# MODBUS_TO_UART.net
KiCad netlist of a schematic drawn in Altium Designer
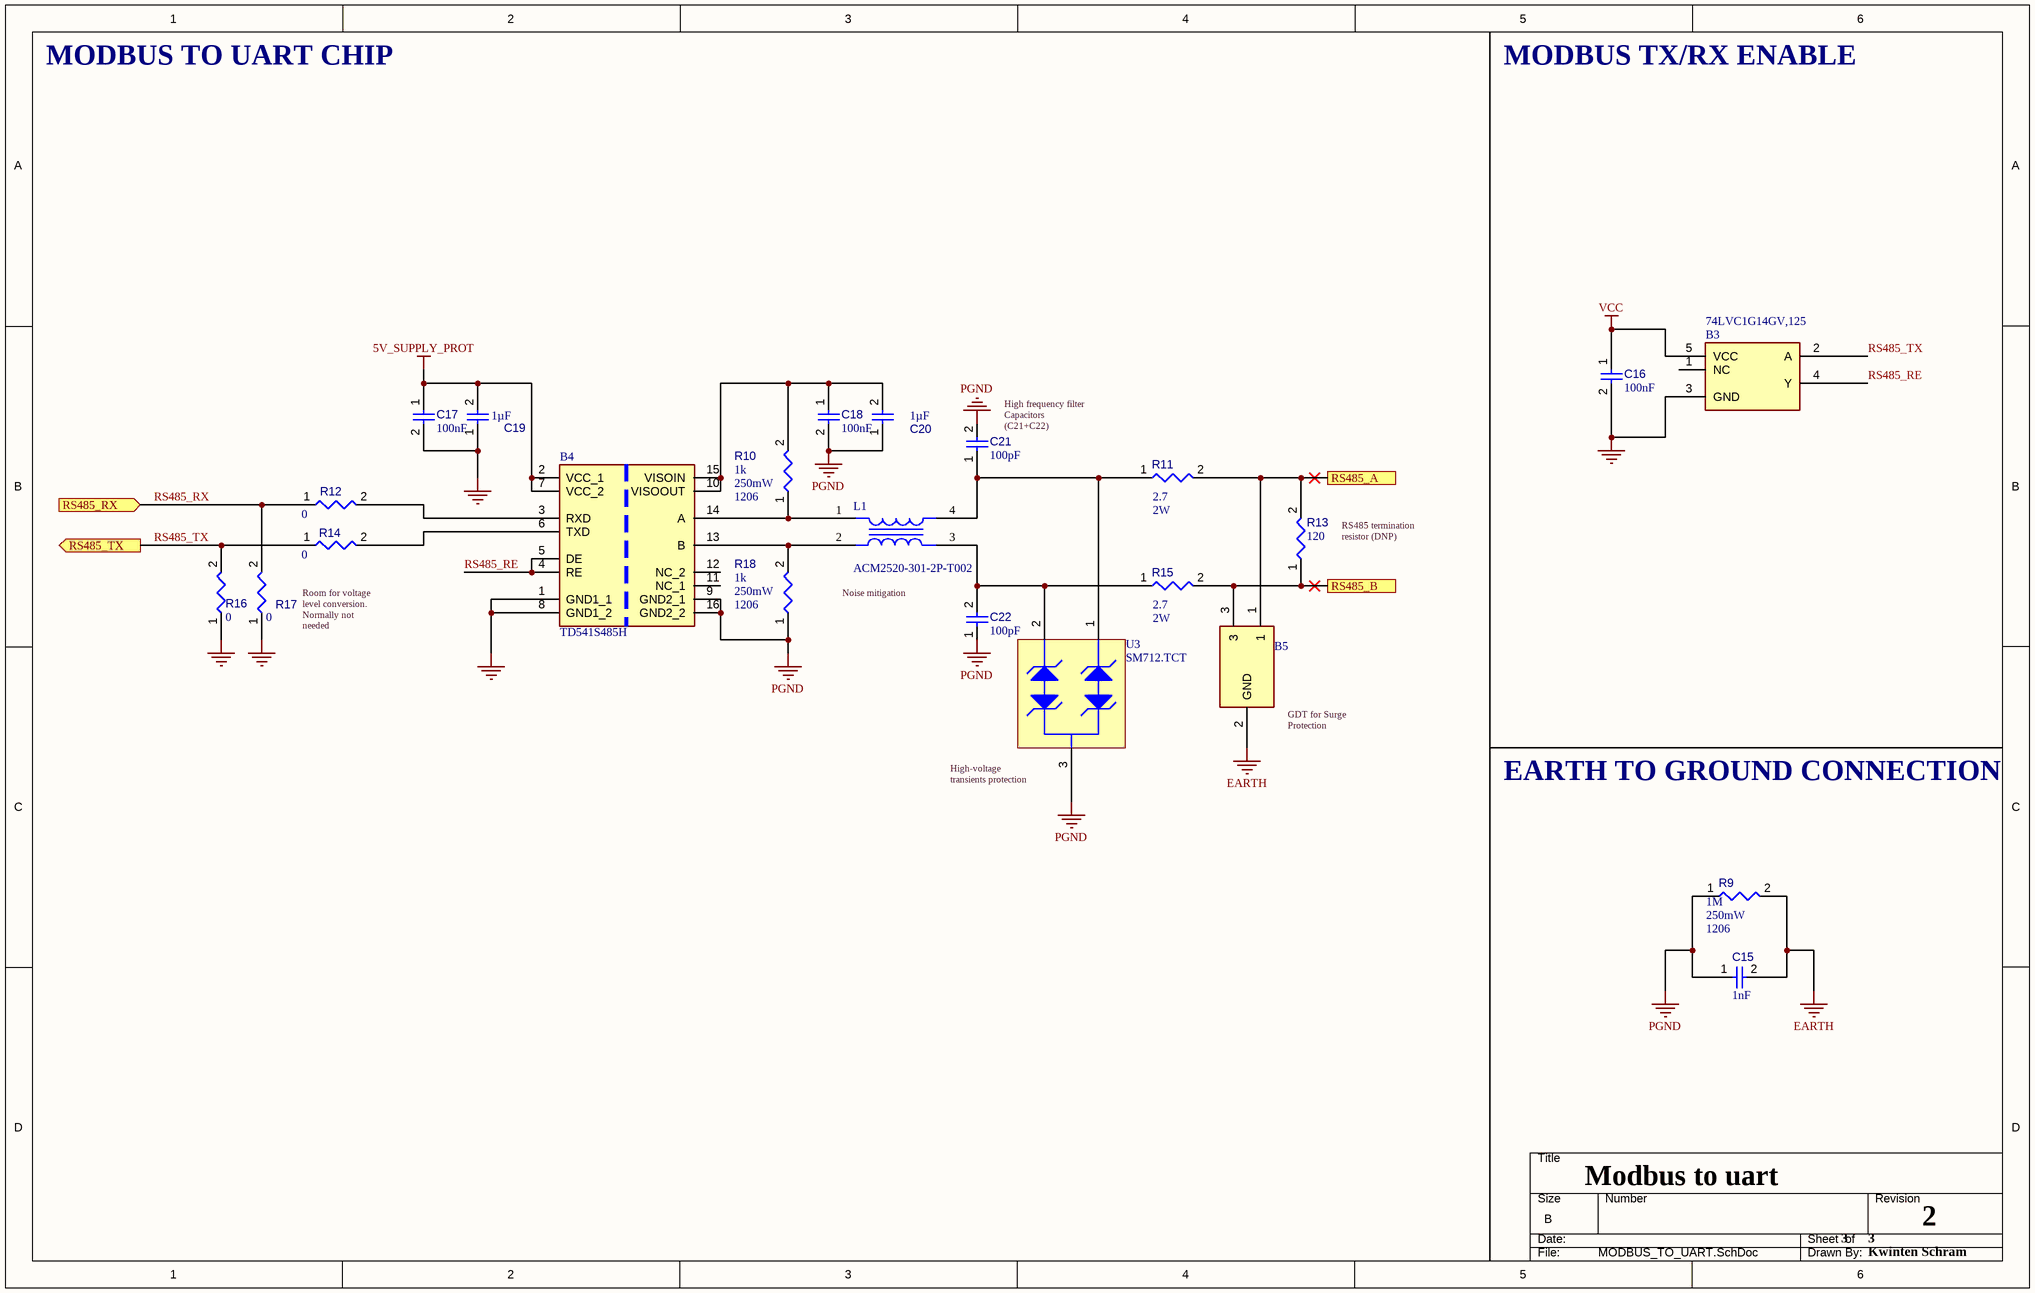
[diagram p0: MODBUS_TO_UART.SchDoc]

(export (version "E")
  (design (tool "Eeschema 10.0.6"))
  (components
    (comp (ref "B3")
      (value "74LVC1G14GV,125")
      (footprint "74LVC1G14GV,125-Footprint-1")
      (description "Inverter, LVC/LCX/Z Series, 1-Func, 1-Input, CMOS, PDSO5")
      (libsource (lib "Altium Concord Pro on A365") (part "74LVC1G14GV,125-Symbol-1"))
    )
    (comp (ref "B4")
      (value "TD541S485H")
      (footprint "TD541S485H-Footprint-1")
      (description "Support Circuit")
      (libsource (lib "Altium Concord Pro on A365") (part "TD541S485H-Symbol-1"))
    )
    (comp (ref "B5")
      (value "3RL090M-5-S")
      (footprint "2036-09-SM-RPLF-H-Footprint-1")
      (description "3R-5-S Series 5 mm 600 V 5 kA Surface Mount Gas Discharge Tube")
      (libsource (lib "Altium Concord Pro on A365") (part "2036-09-SM-RPLF-H-Symbol-1"))
    )
    (comp (ref "C15")
      (value "1nF")
      (footprint "FP-CC1206-0_3-1_45-IPC_A")
      (fields (field (name "TOLERANCE") "10%") (field (name "Comment") "CC1206KKX7RDBB102"))
      (libsource (lib "Altium Concord Pro on A365") (part "CAP-NP-2"))
    )
    (comp (ref "C16")
      (value "100nF")
      (footprint "FP-0603-L_1_6_0_15-W_0_81-MFG")
      (fields (field (name "TOLERANCE") "10%") (field (name "Comment") "06033C104KAT2A"))
      (libsource (lib "Altium Concord Pro on A365") (part "CAP-NP-2"))
    )
    (comp (ref "C17")
      (value "100nF")
      (footprint "FP-0603-L_1_6_0_15-W_0_81-MFG")
      (fields (field (name "TOLERANCE") "10%") (field (name "Comment") "06033C104KAT2A"))
      (libsource (lib "Altium Concord Pro on A365") (part "CAP-NP-2"))
    )
    (comp (ref "C18")
      (value "100nF")
      (footprint "FP-0603-L_1_6_0_15-W_0_81-MFG")
      (fields (field (name "TOLERANCE") "10%") (field (name "Comment") "06033C104KAT2A"))
      (libsource (lib "Altium Concord Pro on A365") (part "CAP-NP-2"))
    )
    (comp (ref "C19")
      (value "1µF")
      (footprint "FP-CC0603-DA-MFG")
      (fields (field (name "TOLERANCE") "10%") (field (name "Comment") "CC0603KPX7R8BB105"))
      (libsource (lib "Altium Concord Pro on A365") (part "CAP-NP-2"))
    )
    (comp (ref "C20")
      (value "1µF")
      (footprint "FP-CC0603-DA-MFG")
      (fields (field (name "TOLERANCE") "10%") (field (name "Comment") "CC0603KPX7R8BB105"))
      (libsource (lib "Altium Concord Pro on A365") (part "CAP-NP-2"))
    )
    (comp (ref "C21")
      (value "100pF")
      (footprint "FP-CC0603-DA-IPC_B")
      (fields (field (name "TOLERANCE") "10%") (field (name "Comment") "CC0603KRX7R9BB101"))
      (libsource (lib "Altium Concord Pro on A365") (part "CAP-NP-2"))
    )
    (comp (ref "C22")
      (value "100pF")
      (footprint "FP-CC0603-DA-IPC_B")
      (fields (field (name "TOLERANCE") "10%") (field (name "Comment") "CC0603KRX7R9BB101"))
      (libsource (lib "Altium Concord Pro on A365") (part "CAP-NP-2"))
    )
    (comp (ref "L1")
      (value "ACM2520-301-2P-T002")
      (footprint "FP-ACM2520-2P-MFG")
      (description "Ferrite Chip, 2 Function(s), 20V, 0.4A, 4 Pin(s)")
      (libsource (lib "Altium Concord Pro on A365") (part "d0b2d54a63b95a1e21836838efe74ed"))
    )
    (comp (ref "R9")
      (value "1M")
      (footprint "RESC3116X65X40ML10T20")
      (description "Fixed Resistor, Thin Film, 0.25W, 1000000ohm, 200V, 1% +/-Tol, 50ppm/Cel, Surface Mount, 1206")
      (fields
        (field (name "POWER") "250mW")
        (field (name "TOLERANCE") "1%")
        (field (name "CASE/PACKAGE") "1206")
        (field (name "Comment") "RT1206FRE071ML")
      )
      (libsource (lib "Altium Concord Pro on A365") (part "RES-2"))
    )
    (comp (ref "R10")
      (value "1k")
      (footprint "FP-CRCW1206-e3-IPC_A")
      (fields
        (field (name "CASE/PACKAGE") "1206")
        (field (name "TOLERANCE") "5%")
        (field (name "POWER") "250mW")
        (field (name "Comment") "CRCW12061K00JNEC")
      )
      (libsource (lib "Altium Concord Pro on A365") (part "RES-2"))
    )
    (comp (ref "R11")
      (value "2.7")
      (footprint "SMW22R7JT-Footprint-1")
      (description "Fixed Resistor, Wire Wound, 2W, 2.7ohm, 300V, 5% +/-Tol, 200ppm/Cel, Surface Mount, 2616")
      (fields
        (field (name "POWER") "2W")
        (field (name "TOLERANCE") "5%")
        (field (name "Comment") "SMW22R7JT")
      )
      (libsource (lib "Altium Concord Pro on A365") (part "RES-2"))
    )
    (comp (ref "R12")
      (value "0")
      (footprint "FP-CRCW0402-e3-IPC_A")
      (description "Metal Glaze/thick Film, 0.063W, 0ohm, Surface Mount, 0402")
      (fields (field (name "POWER") "63mW") (field (name "Comment") "CRCW04020000Z0ED"))
      (libsource (lib "Altium Concord Pro on A365") (part "RES-2"))
    )
    (comp (ref "R13")
      (value "120")
      (footprint "FP-RT0603-IPC_C")
      (description "Fixed Resistor, Thin Film, 0.1W, 120ohm, 75V, 0.5% +/-Tol, 50ppm/Cel, Surface Mount, 0603")
      (fields (field (name "TOLERANCE") "0.5%") (field (name "POWER") "100mW"))
      (libsource (lib "Altium Concord Pro on A365") (part "RES-2"))
    )
    (comp (ref "R14")
      (value "0")
      (footprint "FP-CRCW0402-e3-IPC_A")
      (description "Metal Glaze/thick Film, 0.063W, 0ohm, Surface Mount, 0402")
      (fields (field (name "POWER") "63mW") (field (name "Comment") "CRCW04020000Z0ED"))
      (libsource (lib "Altium Concord Pro on A365") (part "RES-2"))
    )
    (comp (ref "R15")
      (value "2.7")
      (footprint "SMW22R7JT-Footprint-1")
      (description "Fixed Resistor, Wire Wound, 2W, 2.7ohm, 300V, 5% +/-Tol, 200ppm/Cel, Surface Mount, 2616")
      (fields
        (field (name "POWER") "2W")
        (field (name "TOLERANCE") "5%")
        (field (name "Comment") "SMW22R7JT")
      )
      (libsource (lib "Altium Concord Pro on A365") (part "RES-2"))
    )
    (comp (ref "R16")
      (value "0")
      (footprint "FP-CRCW0402-e3-IPC_A")
      (description "Metal Glaze/thick Film, 0.063W, 0ohm, Surface Mount, 0402")
      (fields (field (name "POWER") "63mW") (field (name "Comment") "CRCW04020000Z0ED"))
      (libsource (lib "Altium Concord Pro on A365") (part "RES-2"))
    )
    (comp (ref "R17")
      (value "0")
      (footprint "FP-CRCW0402-e3-IPC_A")
      (description "Metal Glaze/thick Film, 0.063W, 0ohm, Surface Mount, 0402")
      (fields (field (name "POWER") "63mW") (field (name "Comment") "CRCW04020000Z0ED"))
      (libsource (lib "Altium Concord Pro on A365") (part "RES-2"))
    )
    (comp (ref "R18")
      (value "1k")
      (footprint "FP-CRCW1206-e3-IPC_A")
      (fields
        (field (name "CASE/PACKAGE") "1206")
        (field (name "TOLERANCE") "5%")
        (field (name "POWER") "250mW")
        (field (name "Comment") "CRCW12061K00JNEC")
      )
      (libsource (lib "Altium Concord Pro on A365") (part "RES-2"))
    )
    (comp (ref "U3")
      (value "SM712.TCT")
      (footprint "SMTC-SOT23-3_V")
      (description "Trans Voltage Suppressor Diode, 400W, 12V V(RWM), Unidirectional, 4 Element, Silicon")
      (libsource (lib "Altium Concord Pro on A365") (part "SMTC-SM712.TCT-SOT23-3"))
    )
  )
  (nets
    (net (code "1") (name "/RS485_A") (class "Default")
      (node (ref "B5") (pin "1") (pinfunction "1_1") (pintype "passive"))
      (node (ref "R11") (pin "2") (pinfunction "2_2") (pintype "passive"))
      (node (ref "R13") (pin "2") (pinfunction "2_2") (pintype "passive"))
    )
    (net (code "2") (name "/RS485_B") (class "Default")
      (node (ref "B5") (pin "3") (pinfunction "3_3") (pintype "passive"))
      (node (ref "R13") (pin "1") (pinfunction "1_1") (pintype "passive"))
      (node (ref "R15") (pin "2") (pinfunction "2_2") (pintype "passive"))
    )
    (net (code "3") (name "/RS485_RE") (class "Default")
      (node (ref "B3") (pin "4") (pinfunction "Y_4") (pintype "passive"))
      (node (ref "B4") (pin "4") (pinfunction "RE_4") (pintype "passive"))
      (node (ref "B4") (pin "5") (pinfunction "DE_5") (pintype "passive"))
    )
    (net (code "4") (name "/RS485_RX") (class "Default")
      (node (ref "R12") (pin "1") (pinfunction "1_1") (pintype "passive"))
      (node (ref "R17") (pin "2") (pinfunction "2_2") (pintype "passive"))
    )
    (net (code "5") (name "/RS485_TX") (class "Default")
      (node (ref "B3") (pin "2") (pinfunction "A_2") (pintype "passive"))
      (node (ref "R14") (pin "1") (pinfunction "1_1") (pintype "passive"))
      (node (ref "R16") (pin "2") (pinfunction "2_2") (pintype "passive"))
    )
    (net (code "6") (name "5V_SUPPLY_PROT") (class "Default")
      (node (ref "B4") (pin "2") (pinfunction "VCC_1_2") (pintype "passive"))
      (node (ref "B4") (pin "7") (pinfunction "VCC_2_7") (pintype "passive"))
      (node (ref "C17") (pin "1") (pinfunction "1_1") (pintype "passive"))
      (node (ref "C19") (pin "2") (pinfunction "2_2") (pintype "passive"))
    )
    (net (code "7") (name "EARTH") (class "Default")
      (node (ref "B5") (pin "2") (pinfunction "GND_2") (pintype "passive"))
      (node (ref "C15") (pin "2") (pinfunction "2_2") (pintype "passive"))
      (node (ref "R9") (pin "2") (pinfunction "2_2") (pintype "passive"))
    )
    (net (code "8") (name "GND") (class "Default")
      (node (ref "B3") (pin "3") (pinfunction "GND_3") (pintype "passive"))
      (node (ref "B4") (pin "1") (pinfunction "GND1_1_1") (pintype "passive"))
      (node (ref "B4") (pin "8") (pinfunction "GND1_2_8") (pintype "passive"))
      (node (ref "C16") (pin "2") (pinfunction "2_2") (pintype "passive"))
      (node (ref "C17") (pin "2") (pinfunction "2_2") (pintype "passive"))
      (node (ref "C19") (pin "1") (pinfunction "1_1") (pintype "passive"))
      (node (ref "R16") (pin "1") (pinfunction "1_1") (pintype "passive"))
      (node (ref "R17") (pin "1") (pinfunction "1_1") (pintype "passive"))
    )
    (net (code "9") (name "Net-(B4-A)") (class "Default")
      (node (ref "B4") (pin "14") (pinfunction "A_14") (pintype "passive"))
      (node (ref "L1") (pin "1") (pinfunction "1_1") (pintype "passive"))
      (node (ref "R10") (pin "1") (pinfunction "1_1") (pintype "passive"))
    )
    (net (code "10") (name "Net-(B4-B)") (class "Default")
      (node (ref "B4") (pin "13") (pinfunction "B_13") (pintype "passive"))
      (node (ref "L1") (pin "2") (pinfunction "2_2") (pintype "passive"))
      (node (ref "R18") (pin "2") (pinfunction "2_2") (pintype "passive"))
    )
    (net (code "11") (name "Net-(B4-RXD)") (class "Default")
      (node (ref "B4") (pin "3") (pinfunction "RXD_3") (pintype "passive"))
      (node (ref "R12") (pin "2") (pinfunction "2_2") (pintype "passive"))
    )
    (net (code "12") (name "Net-(B4-TXD)") (class "Default")
      (node (ref "B4") (pin "6") (pinfunction "TXD_6") (pintype "passive"))
      (node (ref "R14") (pin "2") (pinfunction "2_2") (pintype "passive"))
    )
    (net (code "13") (name "Net-(B4-VISOIN)") (class "Default")
      (node (ref "B4") (pin "10") (pinfunction "VISOOUT_10") (pintype "passive"))
      (node (ref "B4") (pin "15") (pinfunction "VISOIN_15") (pintype "passive"))
      (node (ref "C18") (pin "1") (pinfunction "1_1") (pintype "passive"))
      (node (ref "C20") (pin "2") (pinfunction "2_2") (pintype "passive"))
      (node (ref "R10") (pin "2") (pinfunction "2_2") (pintype "passive"))
    )
    (net (code "14") (name "Net-(C21-Pad1)") (class "Default")
      (node (ref "C21") (pin "1") (pinfunction "1_1") (pintype "passive"))
      (node (ref "L1") (pin "4") (pinfunction "4_4") (pintype "passive"))
      (node (ref "R11") (pin "1") (pinfunction "1_1") (pintype "passive"))
      (node (ref "U3") (pin "1") (pinfunction "1_1") (pintype "passive"))
    )
    (net (code "15") (name "Net-(C22-Pad2)") (class "Default")
      (node (ref "C22") (pin "2") (pinfunction "2_2") (pintype "passive"))
      (node (ref "L1") (pin "3") (pinfunction "3_3") (pintype "passive"))
      (node (ref "R15") (pin "1") (pinfunction "1_1") (pintype "passive"))
      (node (ref "U3") (pin "2") (pinfunction "2_2") (pintype "passive"))
    )
    (net (code "16") (name "PGND") (class "Default")
      (node (ref "B4") (pin "16") (pinfunction "GND2_2_16") (pintype "passive"))
      (node (ref "B4") (pin "9") (pinfunction "GND2_1_9") (pintype "passive"))
      (node (ref "C15") (pin "1") (pinfunction "1_1") (pintype "passive"))
      (node (ref "C18") (pin "2") (pinfunction "2_2") (pintype "passive"))
      (node (ref "C20") (pin "1") (pinfunction "1_1") (pintype "passive"))
      (node (ref "C21") (pin "2") (pinfunction "2_2") (pintype "passive"))
      (node (ref "C22") (pin "1") (pinfunction "1_1") (pintype "passive"))
      (node (ref "R18") (pin "1") (pinfunction "1_1") (pintype "passive"))
      (node (ref "R9") (pin "1") (pinfunction "1_1") (pintype "passive"))
      (node (ref "U3") (pin "3") (pinfunction "3_3") (pintype "passive"))
    )
    (net (code "17") (name "VCC") (class "Default")
      (node (ref "B3") (pin "5") (pinfunction "VCC_5") (pintype "passive"))
      (node (ref "C16") (pin "1") (pinfunction "1_1") (pintype "passive"))
    )
    (net (code "18") (name "unconnected-(B3-NC-Pad1)") (class "Default")
      (node (ref "B3") (pin "1") (pinfunction "NC_1") (pintype "passive"))
    )
    (net (code "19") (name "unconnected-(B4-NC_1-Pad11)") (class "Default")
      (node (ref "B4") (pin "11") (pinfunction "NC_1_11") (pintype "passive"))
    )
    (net (code "20") (name "unconnected-(B4-NC_2-Pad12)") (class "Default")
      (node (ref "B4") (pin "12") (pinfunction "NC_2_12") (pintype "passive"))
    )
  )
)
